# STM32BluePill.net
KiCad netlist of a schematic drawn in Altium Designer
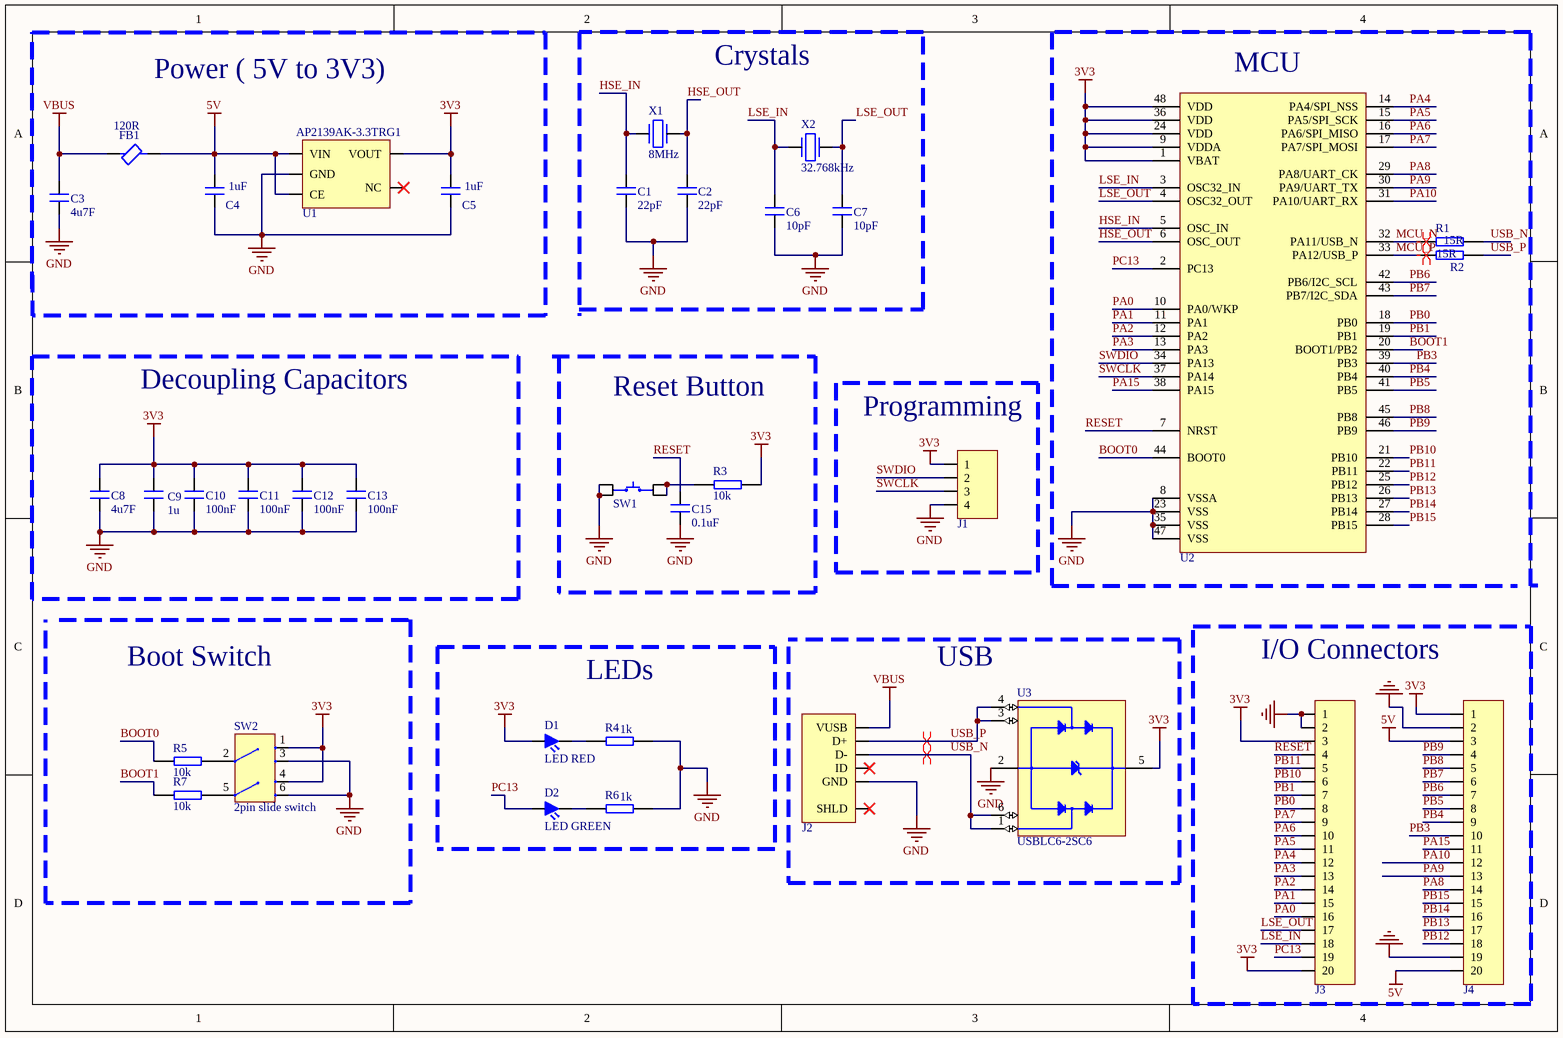
[diagram p0: STM32BluePill.SchDoc]

(export (version "E")
  (design (tool "Eeschema 10.0.6"))
  (components
    (comp (ref "C1")
      (value "22pF")
      (footprint "0402 CAP")
      (fields
        (field (name "MANUFACTURER") "Murata")
        (field (name "MANUFACTURER PART NUMBER") "GRM1555C1H220JA01D")
      )
      (libsource (lib "GenerALI") (part "0402 22p CAP"))
    )
    (comp (ref "C2")
      (value "22pF")
      (footprint "0402 CAP")
      (fields
        (field (name "MANUFACTURER") "Murata")
        (field (name "MANUFACTURER PART NUMBER") "GRM1555C1H220JA01D")
      )
      (libsource (lib "GenerALI") (part "0402 22p CAP"))
    )
    (comp (ref "C3")
      (value "4u7F")
      (footprint "0603 CAP")
      (fields
        (field (name "MANUFACTURER") "Samsung")
        (field (name "MANUFACTURER PART NUMBER") "CL10A475KA8NQNC")
      )
      (libsource (lib "GenerALI") (part "0603 4u7 CAP"))
    )
    (comp (ref "C4")
      (value "1uF")
      (footprint "0603 CAP")
      (fields
        (field (name "MANUFACTURER") "Murata")
        (field (name "MANUFACTURER PART NUMBER") "GCM188R71E105KA64D")
      )
      (libsource (lib "GenerALI") (part "0603 1u CAP"))
    )
    (comp (ref "C5")
      (value "1uF")
      (footprint "0603 CAP")
      (fields
        (field (name "MANUFACTURER") "Murata")
        (field (name "MANUFACTURER PART NUMBER") "GCM188R71E105KA64D")
      )
      (libsource (lib "GenerALI") (part "0603 1u CAP"))
    )
    (comp (ref "C6")
      (value "10pF")
      (footprint "0402 CAP")
      (fields
        (field (name "MANUFACTURER") "Murata")
        (field (name "MANUFACTURER PART NUMBER") "GRM0225C1E100GA03L")
      )
      (libsource (lib "GenerALI") (part "0402 10p CAP"))
    )
    (comp (ref "C7")
      (value "10pF")
      (footprint "0402 CAP")
      (fields
        (field (name "MANUFACTURER") "Murata")
        (field (name "MANUFACTURER PART NUMBER") "GRM0225C1E100GA03L")
      )
      (libsource (lib "GenerALI") (part "0402 10p CAP"))
    )
    (comp (ref "C8")
      (value "4u7F")
      (footprint "0603 CAP")
      (fields
        (field (name "MANUFACTURER") "Samsung")
        (field (name "MANUFACTURER PART NUMBER") "CL10A475KA8NQNC")
      )
      (libsource (lib "GenerALI") (part "0603 4u7 CAP"))
    )
    (comp (ref "C9")
      (value "1u")
      (footprint "0603 CAP")
      (fields
        (field (name "MANUFACTURER") "Murata")
        (field (name "MANUFACTURER PART NUMBER") "GCM188R71E105KA64D")
      )
      (libsource (lib "GenerALI") (part "0603 1u CAP"))
    )
    (comp (ref "C10")
      (value "100nF")
      (footprint "0402 CAP")
      (fields
        (field (name "MANUFACTURER") "Murata")
        (field (name "MANUFACTURER PART NUMBER") "GRM155R71E104KE14J")
      )
      (libsource (lib "GenerALI") (part "0402 100n AP"))
    )
    (comp (ref "C11")
      (value "100nF")
      (footprint "0402 CAP")
      (fields
        (field (name "MANUFACTURER") "Murata")
        (field (name "MANUFACTURER PART NUMBER") "GRM155R71E104KE14J")
      )
      (libsource (lib "GenerALI") (part "0402 100n AP"))
    )
    (comp (ref "C12")
      (value "100nF")
      (footprint "0402 CAP")
      (fields
        (field (name "MANUFACTURER") "Murata")
        (field (name "MANUFACTURER PART NUMBER") "GRM155R71E104KE14J")
      )
      (libsource (lib "GenerALI") (part "0402 100n AP"))
    )
    (comp (ref "C13")
      (value "100nF")
      (footprint "0402 CAP")
      (fields
        (field (name "MANUFACTURER") "Murata")
        (field (name "MANUFACTURER PART NUMBER") "GRM155R71E104KE14J")
      )
      (libsource (lib "GenerALI") (part "0402 100n AP"))
    )
    (comp (ref "C15")
      (value "0.1uF")
      (footprint "0402 CAP")
      (fields
        (field (name "MANUFACTURER") "Murata")
        (field (name "MANUFACTURER PART NUMBER") "GRM155R71E104KE14J")
      )
      (libsource (lib "GenerALI") (part "0402 100n AP"))
    )
    (comp (ref "D1")
      (value "LED RED")
      (footprint "LED 0805")
      (libsource (lib "GenerALI") (part "LED RED 0805"))
    )
    (comp (ref "D2")
      (value "LED GREEN")
      (footprint "LED 0805")
      (libsource (lib "GenerALI") (part "LED GREEN 0805"))
    )
    (comp (ref "FB1")
      (value "120R")
      (footprint "0402 RES")
      (description "Ferrite Chip, 1 Function(s), 0.9A, 2 Pin(s)\r\nBLM15PD121SN1D")
      (fields
        (field (name "MANUFACTURER") "Murata")
        (field (name "MANUFACTURER PART NUMBER") "BLM15PD121SN1D")
      )
      (libsource (lib "GenerALI") (part "Ferritte Bead 120R 0402"))
    )
    (comp (ref "J1")
      (value "Header 2.54MM 4POS 90D Male")
      (footprint "4pin 90degree header 2.54mm")
      (libsource (lib "GenerALI") (part "Header 2.54MM 4POS 90D Male"))
    )
    (comp (ref "J2")
      (value "10118192-0001LF")
      (footprint "10118192-0001LF")
      (description "CONN USB MICRO B RECPT SMT R/A")
      (fields (field (name "MANUFACTURER") "Amphenol ICC / FCI"))
      (libsource (lib "GenerALI") (part "micro b usb connector"))
    )
    (comp (ref "J3")
      (value "Header 2.54MM 20POS Male")
      (footprint "20pin Male Header 2.54mm")
      (libsource (lib "GenerALI") (part "Header 2.54MM 20POS Male"))
    )
    (comp (ref "J4")
      (value "Header 2.54MM 20POS Male")
      (footprint "20pin Male Header 2.54mm")
      (libsource (lib "GenerALI") (part "Header 2.54MM 20POS Male"))
    )
    (comp (ref "R1")
      (value "15R")
      (footprint "0402 RES")
      (fields
        (field (name "MANUFACTURER") "Yageo")
        (field (name "MANUFACTURER PART NUMBER") "RC0402FR-0715RL")
        (field (name "TOLERANCE") "1%")
      )
      (libsource (lib "GenerALI") (part "0402 15R RES"))
    )
    (comp (ref "R2")
      (value "15R")
      (footprint "0402 RES")
      (fields
        (field (name "MANUFACTURER") "Yageo")
        (field (name "MANUFACTURER PART NUMBER") "RC0402FR-0715RL")
        (field (name "TOLERANCE") "1%")
      )
      (libsource (lib "GenerALI") (part "0402 15R RES"))
    )
    (comp (ref "R3")
      (value "10k")
      (footprint "0402 RES")
      (fields
        (field (name "MANUFACTURER") "Samsung")
        (field (name "MANUFACTURER PART NUMBER") "RC1005F103CS")
        (field (name "TOLERANCE") "1%")
      )
      (libsource (lib "GenerALI") (part "0402 10k RES"))
    )
    (comp (ref "R4")
      (value "1k")
      (footprint "0402 RES")
      (fields
        (field (name "MANUFACTURER") "Samsung")
        (field (name "MANUFACTURER PART NUMBER") "RC1005F103CS")
        (field (name "TOLERANCE") "1%")
      )
      (libsource (lib "GenerALI") (part "0402 1k RES"))
    )
    (comp (ref "R5")
      (value "10k")
      (footprint "0402 RES")
      (fields
        (field (name "MANUFACTURER") "Samsung")
        (field (name "MANUFACTURER PART NUMBER") "RC1005F103CS")
        (field (name "TOLERANCE") "1%")
      )
      (libsource (lib "GenerALI") (part "0402 10k RES"))
    )
    (comp (ref "R6")
      (value "1k")
      (footprint "0402 RES")
      (fields
        (field (name "MANUFACTURER") "Samsung")
        (field (name "MANUFACTURER PART NUMBER") "RC1005F103CS")
        (field (name "TOLERANCE") "1%")
      )
      (libsource (lib "GenerALI") (part "0402 1k RES"))
    )
    (comp (ref "R7")
      (value "10k")
      (footprint "0402 RES")
      (fields
        (field (name "MANUFACTURER") "Samsung")
        (field (name "MANUFACTURER PART NUMBER") "RC1005F103CS")
        (field (name "TOLERANCE") "1%")
      )
      (libsource (lib "GenerALI") (part "0402 10k RES"))
    )
    (comp (ref "SW1")
      (value "SWITCH TACTILE")
      (footprint "4 pin tactile switch")
      (fields
        (field (name "MANUFACTURER") "E-Switch")
        (field (name "MANUFACTURER PART NUMBER") "TL3305BF260QG")
      )
      (libsource (lib "GenerALI") (part "SWITCH TACTILE"))
    )
    (comp (ref "SW2")
      (value "2pin slide switch")
      (footprint "CAS-D20TA")
      (description "SWITCH SLIDE SPDTX2 100MA 6V")
      (fields
        (field (name "MANUFACTURER") "Nidec Copal")
        (field (name "MANUFACTURER PART NUMBER") "CAS-D20TA")
      )
      (libsource (lib "GenerALI") (part "2pin slide switch"))
    )
    (comp (ref "U1")
      (value "AP2139AK-3.3TRG1")
      (footprint "SOT-23-5")
      (description "Fixed Positive LDO Regulator, 3.3V, 0.3V Dropout, CMOS, PDSO5")
      (fields (field (name "MANUFACTURER") "Diodes"))
      (libsource (lib "GenerALI") (part "AP2139AK-3.3TRG1"))
    )
    (comp (ref "U2")
      (value "STM32F103C6T6A")
      (footprint "LQFP-48")
      (description "MCU 32-bit STM32F ARM Cortex M3 RISC 32KB Flash 2.5V/3.3V 48-Pin LQFP Tray")
      (fields
        (field (name "MANUFACTURER") "STMicroelectronics")
        (field (name "DESIGNED BY") "Mert Ali Şentürk")
      )
      (libsource (lib "GenerALI") (part "STM32F103C6T6A"))
    )
    (comp (ref "U3")
      (value "USBLC6-2SC6")
      (footprint "SOT23-6")
      (description "Trans Voltage Suppressor Diode, 5V V(RWM), Unidirectional, 1 Element, Silicon")
      (fields (field (name "MANUFACTURER") "STMicroelectronics"))
      (libsource (lib "GenerALI") (part "USB Protection"))
    )
    (comp (ref "X1")
      (value "8MHz")
      (footprint "XR8M000000S416")
      (description "8 MHz ±30ppm Crystal 16pF 80 Ohms 2-SMD, No Lead")
      (libsource (lib "GenerALI") (part "XR8M000000S416"))
    )
    (comp (ref "X2")
      (value "32.768kHz")
      (footprint "ECX-1210")
      (description "Parallel - Fundamental Quartz Crystal, 32.768KHz Nom 7pF ECX-1210")
      (fields
        (field (name "MANUFACTURER") "ECS International")
        (field (name "MANUFACTURER PART NUMBER") "ECS-.327-7-1210-TR")
      )
      (libsource (lib "GenerALI") (part "ECS-.327-7-1210-TR ECX-1210"))
    )
  )
  (nets
    (net (code "1") (name "/BOOT0") (class "Default")
      (node (ref "R5") (pin "1") (pinfunction "1_1") (pintype "passive"))
      (node (ref "U2") (pin "44") (pinfunction "BOOT0_44") (pintype "passive"))
    )
    (net (code "2") (name "/BOOT1") (class "Default")
      (node (ref "R7") (pin "1") (pinfunction "1_1") (pintype "passive"))
      (node (ref "U2") (pin "20") (pinfunction "BOOT1/PB2_20") (pintype "passive"))
    )
    (net (code "3") (name "/HSE_IN") (class "Default")
      (node (ref "C1") (pin "2") (pinfunction "2_2") (pintype "passive"))
      (node (ref "U2") (pin "5") (pinfunction "OSC_IN_5") (pintype "passive"))
      (node (ref "X1") (pin "1") (pinfunction "1_1") (pintype "passive"))
    )
    (net (code "4") (name "/HSE_OUT") (class "Default")
      (node (ref "C2") (pin "2") (pinfunction "2_2") (pintype "passive"))
      (node (ref "U2") (pin "6") (pinfunction "OSC_OUT_6") (pintype "passive"))
      (node (ref "X1") (pin "2") (pinfunction "2_2") (pintype "passive"))
    )
    (net (code "5") (name "/LSE_IN") (class "Default")
      (node (ref "C6") (pin "2") (pinfunction "2_2") (pintype "passive"))
      (node (ref "J3") (pin "18") (pinfunction "18_18") (pintype "passive"))
      (node (ref "U2") (pin "3") (pinfunction "OSC32_IN_3") (pintype "passive"))
      (node (ref "X2") (pin "2") (pinfunction "2_2") (pintype "passive"))
    )
    (net (code "6") (name "/LSE_OUT") (class "Default")
      (node (ref "C7") (pin "2") (pinfunction "2_2") (pintype "passive"))
      (node (ref "J3") (pin "17") (pinfunction "17_17") (pintype "passive"))
      (node (ref "U2") (pin "4") (pinfunction "OSC32_OUT_4") (pintype "passive"))
      (node (ref "X2") (pin "1") (pinfunction "1_1") (pintype "passive"))
    )
    (net (code "7") (name "/MCU_N") (class "Default")
      (node (ref "R1") (pin "2") (pinfunction "2_2") (pintype "passive"))
      (node (ref "U2") (pin "32") (pinfunction "PA11/USB_N_32") (pintype "passive"))
    )
    (net (code "8") (name "/MCU_P") (class "Default")
      (node (ref "R2") (pin "1") (pinfunction "1_1") (pintype "passive"))
      (node (ref "U2") (pin "33") (pinfunction "PA12/USB_P_33") (pintype "passive"))
    )
    (net (code "9") (name "/PA0") (class "Default")
      (node (ref "J3") (pin "16") (pinfunction "16_16") (pintype "passive"))
      (node (ref "U2") (pin "10") (pinfunction "PA0/WKP_10") (pintype "passive"))
    )
    (net (code "10") (name "/PA1") (class "Default")
      (node (ref "J3") (pin "15") (pinfunction "15_15") (pintype "passive"))
      (node (ref "U2") (pin "11") (pinfunction "PA1_11") (pintype "passive"))
    )
    (net (code "11") (name "/PA2") (class "Default")
      (node (ref "J3") (pin "14") (pinfunction "14_14") (pintype "passive"))
      (node (ref "U2") (pin "12") (pinfunction "PA2_12") (pintype "passive"))
    )
    (net (code "12") (name "/PA3") (class "Default")
      (node (ref "J3") (pin "13") (pinfunction "13_13") (pintype "passive"))
      (node (ref "U2") (pin "13") (pinfunction "PA3_13") (pintype "passive"))
    )
    (net (code "13") (name "/PA4") (class "Default")
      (node (ref "J3") (pin "12") (pinfunction "12_12") (pintype "passive"))
      (node (ref "U2") (pin "14") (pinfunction "PA4/SPI_NSS_14") (pintype "passive"))
    )
    (net (code "14") (name "/PA5") (class "Default")
      (node (ref "J3") (pin "11") (pinfunction "11_11") (pintype "passive"))
      (node (ref "U2") (pin "15") (pinfunction "PA5/SPI_SCK_15") (pintype "passive"))
    )
    (net (code "15") (name "/PA6") (class "Default")
      (node (ref "J3") (pin "10") (pinfunction "10_10") (pintype "passive"))
      (node (ref "U2") (pin "16") (pinfunction "PA6/SPI_MISO_16") (pintype "passive"))
    )
    (net (code "16") (name "/PA7") (class "Default")
      (node (ref "J3") (pin "9") (pinfunction "9_9") (pintype "passive"))
      (node (ref "U2") (pin "17") (pinfunction "PA7/SPI_MOSI_17") (pintype "passive"))
    )
    (net (code "17") (name "/PA8") (class "Default")
      (node (ref "J4") (pin "14") (pinfunction "14_14") (pintype "passive"))
      (node (ref "U2") (pin "29") (pinfunction "PA8/UART_CK_29") (pintype "passive"))
    )
    (net (code "18") (name "/PA9") (class "Default")
      (node (ref "J4") (pin "13") (pinfunction "13_13") (pintype "passive"))
      (node (ref "U2") (pin "30") (pinfunction "PA9/UART_TX_30") (pintype "passive"))
    )
    (net (code "19") (name "/PA10") (class "Default")
      (node (ref "J4") (pin "12") (pinfunction "12_12") (pintype "passive"))
      (node (ref "U2") (pin "31") (pinfunction "PA10/UART_RX_31") (pintype "passive"))
    )
    (net (code "20") (name "/PA15") (class "Default")
      (node (ref "J4") (pin "11") (pinfunction "11_11") (pintype "passive"))
      (node (ref "U2") (pin "38") (pinfunction "PA15_38") (pintype "passive"))
    )
    (net (code "21") (name "/PB0") (class "Default")
      (node (ref "J3") (pin "8") (pinfunction "8_8") (pintype "passive"))
      (node (ref "U2") (pin "18") (pinfunction "PB0_18") (pintype "passive"))
    )
    (net (code "22") (name "/PB1") (class "Default")
      (node (ref "J3") (pin "7") (pinfunction "7_7") (pintype "passive"))
      (node (ref "U2") (pin "19") (pinfunction "PB1_19") (pintype "passive"))
    )
    (net (code "23") (name "/PB3") (class "Default")
      (node (ref "J4") (pin "10") (pinfunction "10_10") (pintype "passive"))
      (node (ref "U2") (pin "39") (pinfunction "PB3_39") (pintype "passive"))
    )
    (net (code "24") (name "/PB4") (class "Default")
      (node (ref "J4") (pin "9") (pinfunction "9_9") (pintype "passive"))
      (node (ref "U2") (pin "40") (pinfunction "PB4_40") (pintype "passive"))
    )
    (net (code "25") (name "/PB5") (class "Default")
      (node (ref "J4") (pin "8") (pinfunction "8_8") (pintype "passive"))
      (node (ref "U2") (pin "41") (pinfunction "PB5_41") (pintype "passive"))
    )
    (net (code "26") (name "/PB6") (class "Default")
      (node (ref "J4") (pin "7") (pinfunction "7_7") (pintype "passive"))
      (node (ref "U2") (pin "42") (pinfunction "PB6/I2C_SCL_42") (pintype "passive"))
    )
    (net (code "27") (name "/PB7") (class "Default")
      (node (ref "J4") (pin "6") (pinfunction "6_6") (pintype "passive"))
      (node (ref "U2") (pin "43") (pinfunction "PB7/I2C_SDA_43") (pintype "passive"))
    )
    (net (code "28") (name "/PB8") (class "Default")
      (node (ref "J4") (pin "5") (pinfunction "5_5") (pintype "passive"))
      (node (ref "U2") (pin "45") (pinfunction "PB8_45") (pintype "passive"))
    )
    (net (code "29") (name "/PB9") (class "Default")
      (node (ref "J4") (pin "4") (pinfunction "4_4") (pintype "passive"))
      (node (ref "U2") (pin "46") (pinfunction "PB9_46") (pintype "passive"))
    )
    (net (code "30") (name "/PB10") (class "Default")
      (node (ref "J3") (pin "6") (pinfunction "6_6") (pintype "passive"))
      (node (ref "U2") (pin "21") (pinfunction "PB10_21") (pintype "passive"))
    )
    (net (code "31") (name "/PB11") (class "Default")
      (node (ref "J3") (pin "5") (pinfunction "5_5") (pintype "passive"))
      (node (ref "U2") (pin "22") (pinfunction "PB11_22") (pintype "passive"))
    )
    (net (code "32") (name "/PB12") (class "Default")
      (node (ref "J4") (pin "18") (pinfunction "18_18") (pintype "passive"))
      (node (ref "U2") (pin "25") (pinfunction "PB12_25") (pintype "passive"))
    )
    (net (code "33") (name "/PB13") (class "Default")
      (node (ref "J4") (pin "17") (pinfunction "17_17") (pintype "passive"))
      (node (ref "U2") (pin "26") (pinfunction "PB13_26") (pintype "passive"))
    )
    (net (code "34") (name "/PB14") (class "Default")
      (node (ref "J4") (pin "16") (pinfunction "16_16") (pintype "passive"))
      (node (ref "U2") (pin "27") (pinfunction "PB14_27") (pintype "passive"))
    )
    (net (code "35") (name "/PB15") (class "Default")
      (node (ref "J4") (pin "15") (pinfunction "15_15") (pintype "passive"))
      (node (ref "U2") (pin "28") (pinfunction "PB15_28") (pintype "passive"))
    )
    (net (code "36") (name "/PC13") (class "Default")
      (node (ref "D2") (pin "2") (pinfunction "2_2") (pintype "passive"))
      (node (ref "J3") (pin "19") (pinfunction "19_19") (pintype "passive"))
      (node (ref "U2") (pin "2") (pinfunction "PC13_2") (pintype "passive"))
    )
    (net (code "37") (name "/RESET") (class "Default")
      (node (ref "C15") (pin "2") (pinfunction "2_2") (pintype "passive"))
      (node (ref "J3") (pin "4") (pinfunction "4_4") (pintype "passive"))
      (node (ref "U2") (pin "7") (pinfunction "NRST_7") (pintype "passive"))
    )
    (net (code "38") (name "/SWCLK") (class "Default")
      (node (ref "J1") (pin "3") (pinfunction "3_3") (pintype "passive"))
      (node (ref "U2") (pin "37") (pinfunction "PA14_37") (pintype "passive"))
    )
    (net (code "39") (name "/SWDIO") (class "Default")
      (node (ref "J1") (pin "2") (pinfunction "2_2") (pintype "passive"))
      (node (ref "U2") (pin "34") (pinfunction "PA13_34") (pintype "passive"))
    )
    (net (code "40") (name "/USB_N") (class "Default")
      (node (ref "J2") (pin "3") (pinfunction "D-_3") (pintype "passive"))
      (node (ref "R1") (pin "1") (pinfunction "1_1") (pintype "passive"))
      (node (ref "U3") (pin "1") (pinfunction "I/O1_1") (pintype "bidirectional"))
      (node (ref "U3") (pin "6") (pinfunction "I/O1_6") (pintype "bidirectional"))
    )
    (net (code "41") (name "/USB_P") (class "Default")
      (node (ref "J2") (pin "2") (pinfunction "D+_2") (pintype "passive"))
      (node (ref "R2") (pin "2") (pinfunction "2_2") (pintype "passive"))
      (node (ref "U3") (pin "3") (pinfunction "I/O2_3") (pintype "bidirectional"))
      (node (ref "U3") (pin "4") (pinfunction "I/O2_4") (pintype "bidirectional"))
    )
    (net (code "42") (name "3V3") (class "Default")
      (node (ref "C10") (pin "2") (pinfunction "2_2") (pintype "passive"))
      (node (ref "C11") (pin "2") (pinfunction "2_2") (pintype "passive"))
      (node (ref "C12") (pin "2") (pinfunction "2_2") (pintype "passive"))
      (node (ref "C13") (pin "2") (pinfunction "2_2") (pintype "passive"))
      (node (ref "C5") (pin "2") (pinfunction "2_2") (pintype "passive"))
      (node (ref "C8") (pin "2") (pinfunction "2_2") (pintype "passive"))
      (node (ref "C9") (pin "2") (pinfunction "2_2") (pintype "passive"))
      (node (ref "D1") (pin "2") (pinfunction "2_2") (pintype "passive"))
      (node (ref "J1") (pin "1") (pinfunction "1_1") (pintype "passive"))
      (node (ref "J3") (pin "20") (pinfunction "20_20") (pintype "passive"))
      (node (ref "J3") (pin "3") (pinfunction "3_3") (pintype "passive"))
      (node (ref "J4") (pin "1") (pinfunction "1_1") (pintype "passive"))
      (node (ref "R3") (pin "2") (pinfunction "2_2") (pintype "passive"))
      (node (ref "SW2") (pin "1") (pinfunction "1_1") (pintype "passive"))
      (node (ref "SW2") (pin "4") (pinfunction "4_4") (pintype "passive"))
      (node (ref "U1") (pin "5") (pinfunction "VOUT_5") (pintype "passive"))
      (node (ref "U2") (pin "1") (pinfunction "VBAT_1") (pintype "passive"))
      (node (ref "U2") (pin "24") (pinfunction "VDD_24") (pintype "passive"))
      (node (ref "U2") (pin "36") (pinfunction "VDD_36") (pintype "passive"))
      (node (ref "U2") (pin "48") (pinfunction "VDD_48") (pintype "passive"))
      (node (ref "U2") (pin "9") (pinfunction "VDDA_9") (pintype "passive"))
      (node (ref "U3") (pin "5") (pinfunction "VBUS_5") (pintype "power_in"))
    )
    (net (code "43") (name "5V") (class "Default")
      (node (ref "C4") (pin "2") (pinfunction "2_2") (pintype "passive"))
      (node (ref "FB1") (pin "2") (pinfunction "2_2") (pintype "passive"))
      (node (ref "J4") (pin "20") (pinfunction "20_20") (pintype "passive"))
      (node (ref "J4") (pin "3") (pinfunction "3_3") (pintype "passive"))
      (node (ref "U1") (pin "1") (pinfunction "VIN_1") (pintype "passive"))
      (node (ref "U1") (pin "3") (pinfunction "CE_3") (pintype "passive"))
    )
    (net (code "44") (name "GND") (class "Default")
      (node (ref "C1") (pin "1") (pinfunction "1_1") (pintype "passive"))
      (node (ref "C10") (pin "1") (pinfunction "1_1") (pintype "passive"))
      (node (ref "C11") (pin "1") (pinfunction "1_1") (pintype "passive"))
      (node (ref "C12") (pin "1") (pinfunction "1_1") (pintype "passive"))
      (node (ref "C13") (pin "1") (pinfunction "1_1") (pintype "passive"))
      (node (ref "C15") (pin "1") (pinfunction "1_1") (pintype "passive"))
      (node (ref "C2") (pin "1") (pinfunction "1_1") (pintype "passive"))
      (node (ref "C3") (pin "1") (pinfunction "1_1") (pintype "passive"))
      (node (ref "C4") (pin "1") (pinfunction "1_1") (pintype "passive"))
      (node (ref "C5") (pin "1") (pinfunction "1_1") (pintype "passive"))
      (node (ref "C6") (pin "1") (pinfunction "1_1") (pintype "passive"))
      (node (ref "C7") (pin "1") (pinfunction "1_1") (pintype "passive"))
      (node (ref "C8") (pin "1") (pinfunction "1_1") (pintype "passive"))
      (node (ref "C9") (pin "1") (pinfunction "1_1") (pintype "passive"))
      (node (ref "J1") (pin "4") (pinfunction "4_4") (pintype "passive"))
      (node (ref "J2") (pin "5") (pinfunction "GND_5") (pintype "passive"))
      (node (ref "J3") (pin "1") (pinfunction "1_1") (pintype "passive"))
      (node (ref "J3") (pin "2") (pinfunction "2_2") (pintype "passive"))
      (node (ref "J4") (pin "19") (pinfunction "19_19") (pintype "passive"))
      (node (ref "J4") (pin "2") (pinfunction "2_2") (pintype "passive"))
      (node (ref "R4") (pin "2") (pinfunction "2_2") (pintype "passive"))
      (node (ref "R6") (pin "2") (pinfunction "2_2") (pintype "passive"))
      (node (ref "SW1") (pin "1") (pinfunction "1_1") (pintype "passive"))
      (node (ref "SW1") (pin "3") (pinfunction "3_3") (pintype "passive"))
      (node (ref "SW2") (pin "3") (pinfunction "3_3") (pintype "passive"))
      (node (ref "SW2") (pin "6") (pinfunction "6_6") (pintype "passive"))
      (node (ref "U1") (pin "2") (pinfunction "GND_2") (pintype "passive"))
      (node (ref "U2") (pin "23") (pinfunction "VSS_23") (pintype "passive"))
      (node (ref "U2") (pin "35") (pinfunction "VSS_35") (pintype "passive"))
      (node (ref "U2") (pin "47") (pinfunction "VSS_47") (pintype "passive"))
      (node (ref "U2") (pin "8") (pinfunction "VSSA_8") (pintype "passive"))
      (node (ref "U3") (pin "2") (pinfunction "GND_2") (pintype "power_in"))
    )
    (net (code "45") (name "Net-(D1-Pad1)") (class "Default")
      (node (ref "D1") (pin "1") (pinfunction "1_1") (pintype "passive"))
      (node (ref "R4") (pin "1") (pinfunction "1_1") (pintype "passive"))
    )
    (net (code "46") (name "Net-(D2-Pad1)") (class "Default")
      (node (ref "D2") (pin "1") (pinfunction "1_1") (pintype "passive"))
      (node (ref "R6") (pin "1") (pinfunction "1_1") (pintype "passive"))
    )
    (net (code "47") (name "Net-(R3-Pad1)") (class "Default")
      (node (ref "R3") (pin "1") (pinfunction "1_1") (pintype "passive"))
      (node (ref "SW1") (pin "2") (pinfunction "2_2") (pintype "passive"))
      (node (ref "SW1") (pin "4") (pinfunction "4_4") (pintype "passive"))
    )
    (net (code "48") (name "Net-(R5-Pad2)") (class "Default")
      (node (ref "R5") (pin "2") (pinfunction "2_2") (pintype "passive"))
      (node (ref "SW2") (pin "2") (pinfunction "2_2") (pintype "passive"))
    )
    (net (code "49") (name "Net-(R7-Pad2)") (class "Default")
      (node (ref "R7") (pin "2") (pinfunction "2_2") (pintype "passive"))
      (node (ref "SW2") (pin "5") (pinfunction "5_5") (pintype "passive"))
    )
    (net (code "50") (name "VBUS") (class "Default")
      (node (ref "C3") (pin "2") (pinfunction "2_2") (pintype "passive"))
      (node (ref "FB1") (pin "1") (pinfunction "1_1") (pintype "passive"))
      (node (ref "J2") (pin "1") (pinfunction "VUSB_1") (pintype "passive"))
    )
    (net (code "51") (name "unconnected-(J2-ID-Pad4)") (class "Default")
      (node (ref "J2") (pin "4") (pinfunction "ID_4") (pintype "passive+no_connect"))
    )
    (net (code "52") (name "unconnected-(J2-SHLD-Pad6)") (class "Default")
      (node (ref "J2") (pin "6") (pinfunction "SHLD_6") (pintype "passive+no_connect"))
    )
    (net (code "53") (name "unconnected-(U1-NC-Pad4)") (class "Default")
      (node (ref "U1") (pin "4") (pinfunction "NC_4") (pintype "passive+no_connect"))
    )
  )
)
